# YOTSUBA_GNSS-receiver_Orion_ver_1_6_1.net
KiCad netlist of a schematic drawn in EAGLE
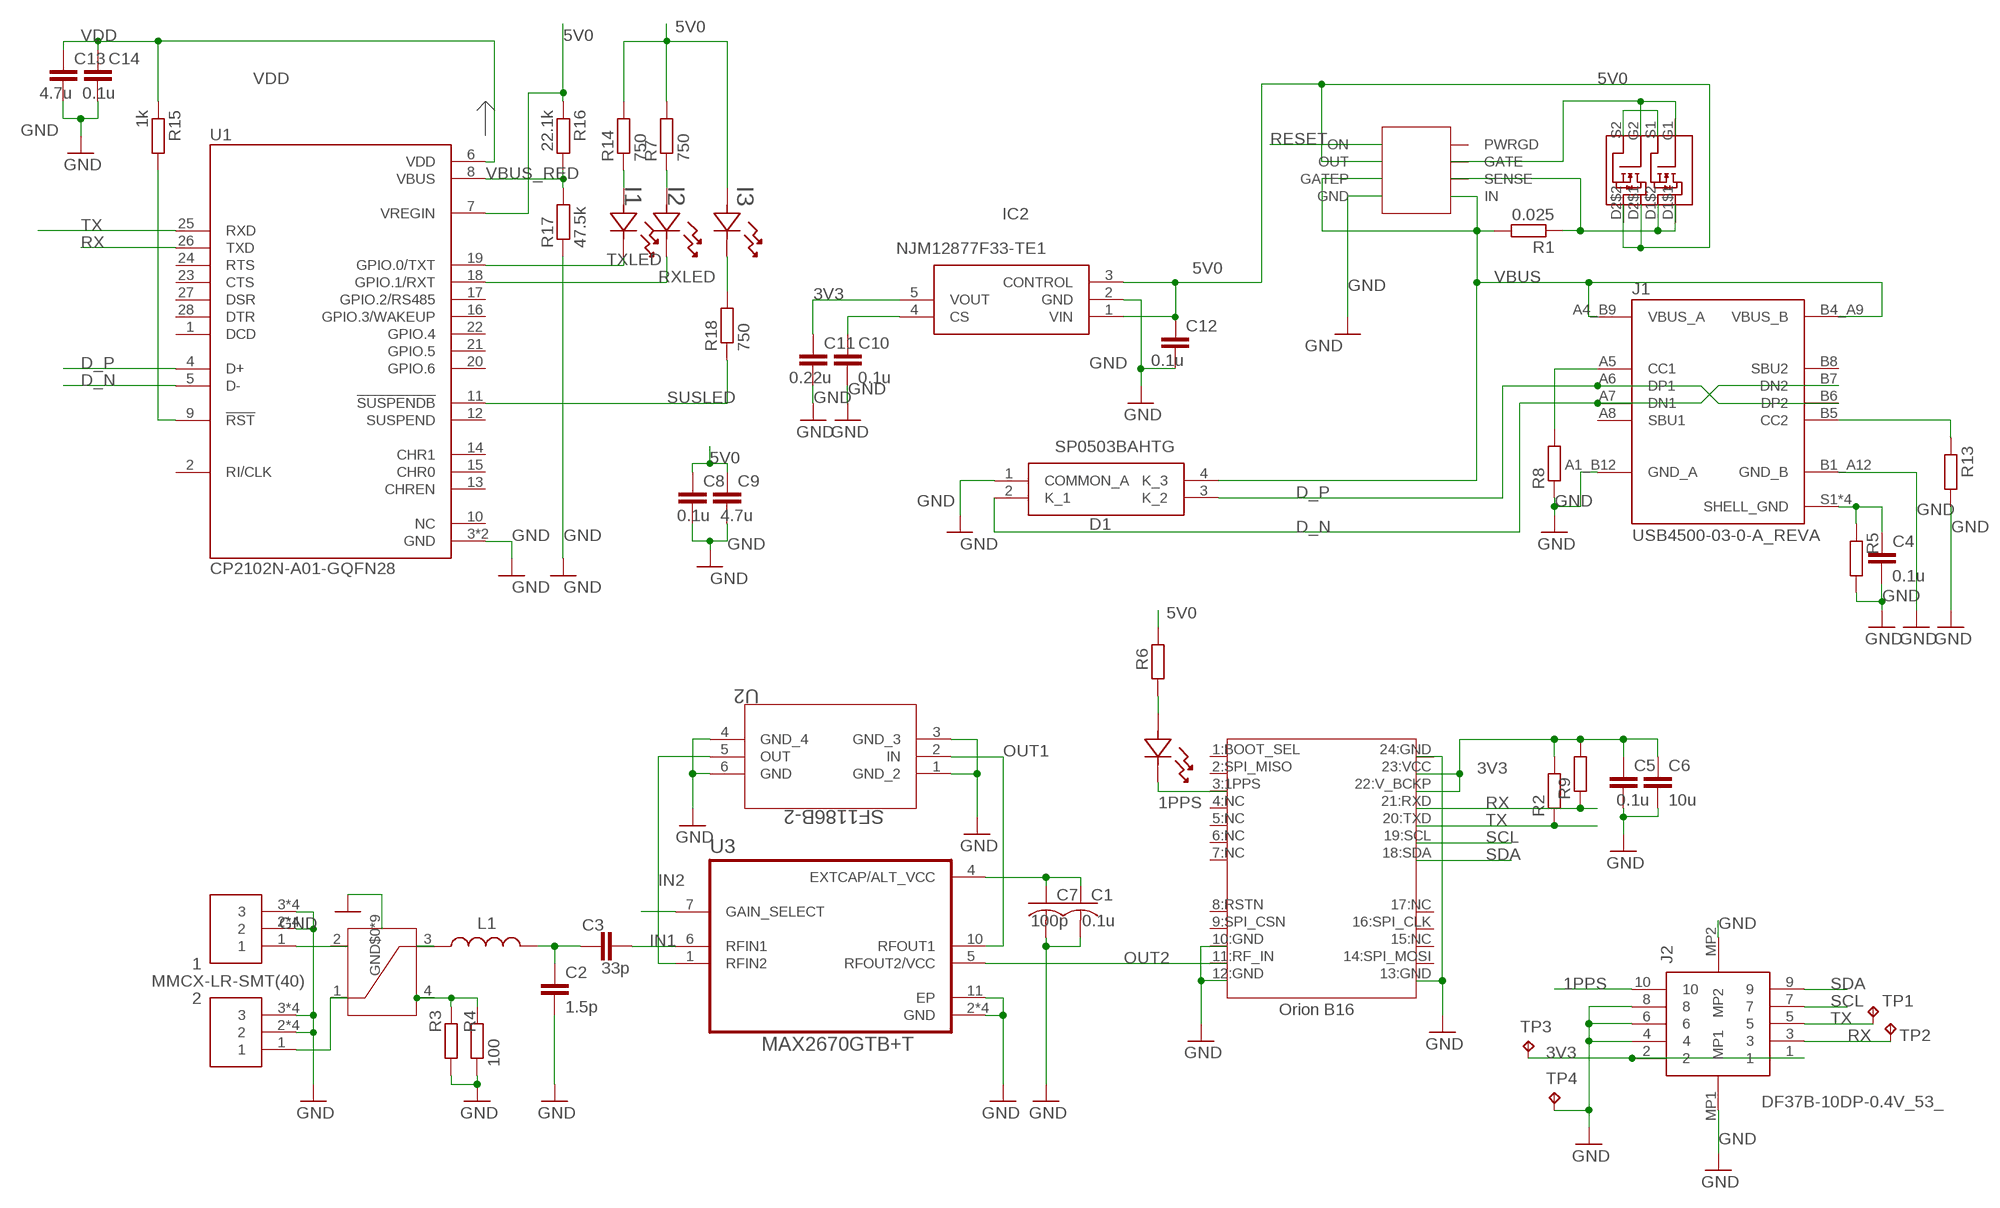
[diagram p0: schematic, sheet 1]

(export (version "E")
  (design (tool "Eeschema 10.0.6"))
  (components
    (comp (ref "1")
      (value "MMCX-LR-SMT(40)")
      (footprint "eagle-import:MMCX-LR-SMT(40)")
      (libsource (lib "eagle-import") (part "MMCX-LR-SMT(40)"))
    )
    (comp (ref "2")
      (value "MMCX-LR-SMT(40)")
      (footprint "eagle-import:MMCX-LR-SMT(40)")
      (libsource (lib "eagle-import") (part "MMCX-LR-SMT(40)"))
    )
    (comp (ref "C1")
      (value "0.1u")
      (footprint "eagle-import:C1608_OS")
      (libsource (lib "eagle-import") (part "C-US"))
    )
    (comp (ref "C2")
      (value "1.5p")
      (footprint "eagle-import:C1608")
      (libsource (lib "eagle-import") (part "C-EUC1608"))
    )
    (comp (ref "C3")
      (value "33p")
      (footprint "eagle-import:C1608")
      (libsource (lib "eagle-import") (part "C-EUC1608"))
    )
    (comp (ref "C4")
      (value "0.1u")
      (footprint "eagle-import:C1608")
      (libsource (lib "eagle-import") (part "C-EUC1608"))
    )
    (comp (ref "C5")
      (value "0.1u")
      (footprint "eagle-import:C1608")
      (libsource (lib "eagle-import") (part "C-EUC1608"))
    )
    (comp (ref "C6")
      (value "10u")
      (footprint "eagle-import:C1608")
      (libsource (lib "eagle-import") (part "C-EUC1608"))
    )
    (comp (ref "C7")
      (value "100p")
      (footprint "eagle-import:C1608_OS")
      (libsource (lib "eagle-import") (part "C-US"))
    )
    (comp (ref "C8")
      (value "0.1u")
      (footprint "eagle-import:C1608")
      (libsource (lib "eagle-import") (part "C-EUC1608"))
    )
    (comp (ref "C9")
      (value "4.7u")
      (footprint "eagle-import:C1608")
      (libsource (lib "eagle-import") (part "C-EUC1608"))
    )
    (comp (ref "C10")
      (value "0.1u")
      (footprint "eagle-import:C1608")
      (libsource (lib "eagle-import") (part "C-EUC1608"))
    )
    (comp (ref "C11")
      (value "0.22u")
      (footprint "eagle-import:C1608")
      (libsource (lib "eagle-import") (part "C-EUC1608"))
    )
    (comp (ref "C12")
      (value "0.1u")
      (footprint "eagle-import:C1608")
      (libsource (lib "eagle-import") (part "C-EUC1608"))
    )
    (comp (ref "C13")
      (value "4.7u")
      (footprint "eagle-import:C1608")
      (libsource (lib "eagle-import") (part "C-EUC1608"))
    )
    (comp (ref "C14")
      (value "0.1u")
      (footprint "eagle-import:C1608")
      (libsource (lib "eagle-import") (part "C-EUC1608"))
    )
    (comp (ref "D1")
      (value "SP0503BAHTG")
      (footprint "eagle-import:SP0503BAHTG")
      (fields (field (name "MOUSER_PART_NUMBER") "576-SP0503BAHTG"))
      (libsource (lib "eagle-import") (part "SP0503BAHTG"))
    )
    (comp (ref "I1")
      (value "SML-E12P8WT86")
      (footprint "eagle-import:LED_SMLD12_ROM")
      (fields (field (name "COPYRIGHT") "Copyright (C) 2023 Ultra Librarian. All rights reserved."))
      (libsource (lib "eagle-import") (part "SML-E12P8WT86"))
    )
    (comp (ref "I2")
      (value "SML-E12P8WT86")
      (footprint "eagle-import:LED_SMLD12_ROM")
      (fields (field (name "COPYRIGHT") "Copyright (C) 2023 Ultra Librarian. All rights reserved."))
      (libsource (lib "eagle-import") (part "SML-E12P8WT86"))
    )
    (comp (ref "I3")
      (value "SML-E12P8WT86")
      (footprint "eagle-import:LED_SMLD12_ROM")
      (fields (field (name "COPYRIGHT") "Copyright (C) 2023 Ultra Librarian. All rights reserved."))
      (libsource (lib "eagle-import") (part "SML-E12P8WT86"))
    )
    (comp (ref "IC2")
      (value "NJM12877F33-TE1")
      (footprint "eagle-import:SOT95P280X120-5N")
      (fields (field (name "MOUSER_PART_NUMBER") "513-NJM12877F33-TE1"))
      (libsource (lib "eagle-import") (part "NJM12877F33-TE1"))
    )
    (comp (ref "J1")
      (value "USB4500-03-0-A_REVA")
      (footprint "eagle-import:GCT_USB4500-03-0-A_REVA")
      (fields
        (field (name "DIGI-KEY_PART_NUMBER") "2073-USB4500-03-0-ATR-ND")
        (field (name "MF") "Global Connector Technology")
        (field (name "MP") "USB4500-03-0-A")
      )
      (libsource (lib "eagle-import") (part "USB4500-03-0-A_REVA"))
    )
    (comp (ref "J2")
      (value "DF37B-10DP-0.4V_53_")
      (footprint "eagle-import:DF37B10DP04V53")
      (fields
        (field (name "MANUFACTURER_PART_NUMBER") "DF37B-10DP-0.4V(53)")
        (field (name "MOUSER_PART_NUMBER") "798-DF37B10DP04V53")
      )
      (libsource (lib "eagle-import") (part "DF37B-10DP-0.4V_53_"))
    )
    (comp (ref "L1")
      (value "4.3n")
      (footprint "eagle-import:INDC1608X100N")
      (fields
        (field (name "DIGIKEY_PART_NUMBER") "490-6896-2-ND")
        (field (name "MF") "Murata")
        (field (name "MP") "LQW18AN4N3C00D")
      )
      (libsource (lib "eagle-import") (part "LQW18AN4N3C00D"))
    )
    (comp (ref "R1")
      (value "0.025")
      (footprint "eagle-import:R0603")
      (libsource (lib "eagle-import") (part "R-EU_R0603"))
    )
    (comp (ref "R2")
      (value "R-EU_R0603")
      (footprint "eagle-import:R0603")
      (libsource (lib "eagle-import") (part "R-EU_R0603"))
    )
    (comp (ref "R3")
      (value "100")
      (footprint "eagle-import:R0603")
      (libsource (lib "eagle-import") (part "R-EU_R0603"))
    )
    (comp (ref "R4")
      (value "100")
      (footprint "eagle-import:R0603")
      (libsource (lib "eagle-import") (part "R-EU_R0603"))
    )
    (comp (ref "R5")
      (value "R-EU_R0603")
      (footprint "eagle-import:R0603")
      (libsource (lib "eagle-import") (part "R-EU_R0603"))
    )
    (comp (ref "R6")
      (value "R-EU_R0603")
      (footprint "eagle-import:R0603")
      (libsource (lib "eagle-import") (part "R-EU_R0603"))
    )
    (comp (ref "R7")
      (value "750")
      (footprint "eagle-import:R0603")
      (libsource (lib "eagle-import") (part "R-EU_R0603"))
    )
    (comp (ref "R8")
      (value "R-EU_R0603")
      (footprint "eagle-import:R0603")
      (libsource (lib "eagle-import") (part "R-EU_R0603"))
    )
    (comp (ref "R9")
      (value "R-EU_R0603")
      (footprint "eagle-import:R0603")
      (libsource (lib "eagle-import") (part "R-EU_R0603"))
    )
    (comp (ref "R10")
      (value "SML-E12P8WT86")
      (footprint "eagle-import:LED_SMLD12_ROM")
      (fields (field (name "COPYRIGHT") "Copyright (C) 2023 Ultra Librarian. All rights reserved."))
      (libsource (lib "eagle-import") (part "SML-E12P8WT86"))
    )
    (comp (ref "R13")
      (value "R-EU_R0603")
      (footprint "eagle-import:R0603")
      (libsource (lib "eagle-import") (part "R-EU_R0603"))
    )
    (comp (ref "R14")
      (value "750")
      (footprint "eagle-import:R0603")
      (libsource (lib "eagle-import") (part "R-EU_R0603"))
    )
    (comp (ref "R15")
      (value "1k")
      (footprint "eagle-import:R0603")
      (libsource (lib "eagle-import") (part "R-EU_R0603"))
    )
    (comp (ref "R16")
      (value "22.1k")
      (footprint "eagle-import:R0603")
      (libsource (lib "eagle-import") (part "R-EU_R0603"))
    )
    (comp (ref "R17")
      (value "47.5k")
      (footprint "eagle-import:R0603")
      (libsource (lib "eagle-import") (part "R-EU_R0603"))
    )
    (comp (ref "R18")
      (value "750")
      (footprint "eagle-import:R0603")
      (libsource (lib "eagle-import") (part "R-EU_R0603"))
    )
    (comp (ref "TP1")
      (value "TPTP13SQ")
      (footprint "eagle-import:TP13SQ")
      (libsource (lib "eagle-import") (part "TPTP13SQ"))
    )
    (comp (ref "TP2")
      (value "TPTP13SQ")
      (footprint "eagle-import:TP13SQ")
      (libsource (lib "eagle-import") (part "TPTP13SQ"))
    )
    (comp (ref "TP3")
      (value "TPTP13SQ")
      (footprint "eagle-import:TP13SQ")
      (libsource (lib "eagle-import") (part "TPTP13SQ"))
    )
    (comp (ref "TP4")
      (value "TPTP13SQ")
      (footprint "eagle-import:TP13SQ")
      (libsource (lib "eagle-import") (part "TPTP13SQ"))
    )
    (comp (ref "U$1")
      (value "ORION_B16")
      (footprint "eagle-import:ORION_B16")
      (libsource (lib "eagle-import") (part "ORION_B16"))
    )
    (comp (ref "U$3")
      (value "HC125.A")
      (footprint "eagle-import:HC125.A")
      (libsource (lib "eagle-import") (part "HC125.A"))
    )
    (comp (ref "U$7")
      (value "DMG6898LSD")
      (footprint "eagle-import:SOIC127P600X150-8N")
      (libsource (lib "eagle-import") (part "DMG6898LSD"))
    )
    (comp (ref "U$8")
      (value "LTC4361")
      (footprint "eagle-import:SOP65P280X100-8N")
      (libsource (lib "eagle-import") (part "LTC4361"))
    )
    (comp (ref "U1")
      (value "CP2102N-A01-GQFN28")
      (footprint "eagle-import:QFN50P500X500X80-29N")
      (fields (field (name "MF") "Silicon Labs"))
      (libsource (lib "eagle-import") (part "CP2102N-A01-GQFN28"))
    )
    (comp (ref "U2")
      (value "SF1186B-2")
      (footprint "eagle-import:SM3030_MUR")
      (fields (field (name "COPYRIGHT") "Copyright (C) 2023 Ultra Librarian. All rights reserved."))
      (libsource (lib "eagle-import") (part "SF1186B-2"))
    )
    (comp (ref "U3")
      (value "MAX2670GTB+T")
      (footprint "eagle-import:DFN300X300X80-11N")
      (fields (field (name "MF") "Analog Devices"))
      (libsource (lib "eagle-import") (part "MAX2670GTB+T"))
    )
  )
  (nets
    (net (code "1") (name "/1PPS") (class "Default")
      (node (ref "J2") (pin "10") (pinfunction "10_10") (pintype "bidirectional"))
      (node (ref "R10") (pin "1") (pinfunction "1_1") (pintype "passive"))
      (node (ref "U$1") (pin "3:1PPS") (pinfunction "3:1PPS_3:1PPS") (pintype "bidirectional"))
    )
    (net (code "2") (name "/3V3") (class "Default")
      (node (ref "C11") (pin "1") (pinfunction "1_1") (pintype "passive"))
      (node (ref "C5") (pin "1") (pinfunction "1_1") (pintype "passive"))
      (node (ref "C6") (pin "1") (pinfunction "1_1") (pintype "passive"))
      (node (ref "IC2") (pin "5") (pinfunction "VOUT_5") (pintype "bidirectional"))
      (node (ref "J2") (pin "1") (pinfunction "1_1") (pintype "bidirectional"))
      (node (ref "J2") (pin "2") (pinfunction "2_2") (pintype "bidirectional"))
      (node (ref "R2") (pin "2") (pinfunction "2_2") (pintype "passive"))
      (node (ref "R9") (pin "2") (pinfunction "2_2") (pintype "passive"))
      (node (ref "TP3") (pin "TP") (pinfunction "TP_TP") (pintype "input"))
      (node (ref "U$1") (pin "22:V_BCKP") (pinfunction "22:V_BCKP_22:V_BCKP") (pintype "bidirectional"))
      (node (ref "U$1") (pin "23:VCC") (pinfunction "23:VCC_23:VCC") (pintype "bidirectional"))
    )
    (net (code "3") (name "/5V0") (class "Default")
      (node (ref "C12") (pin "1") (pinfunction "1_1") (pintype "passive"))
      (node (ref "C8") (pin "1") (pinfunction "1_1") (pintype "passive"))
      (node (ref "C9") (pin "1") (pinfunction "1_1") (pintype "passive"))
      (node (ref "I3") (pin "2") (pinfunction "2_2") (pintype "passive"))
      (node (ref "IC2") (pin "1") (pinfunction "VIN_1") (pintype "bidirectional"))
      (node (ref "IC2") (pin "3") (pinfunction "CONTROL_3") (pintype "bidirectional"))
      (node (ref "R14") (pin "2") (pinfunction "2_2") (pintype "passive"))
      (node (ref "R16") (pin "1") (pinfunction "1_1") (pintype "passive"))
      (node (ref "R6") (pin "2") (pinfunction "2_2") (pintype "passive"))
      (node (ref "R7") (pin "2") (pinfunction "2_2") (pintype "passive"))
      (node (ref "U$7") (pin "D2$1") (pinfunction "D2$1_D2$1") (pintype "bidirectional"))
      (node (ref "U$7") (pin "D2$2") (pinfunction "D2$2_D2$2") (pintype "bidirectional"))
      (node (ref "U$8") (pin "OUT") (pinfunction "OUT_OUT") (pintype "bidirectional"))
      (node (ref "U1") (pin "7") (pinfunction "VREGIN_7") (pintype "power_in"))
    )
    (net (code "4") (name "/D_N") (class "Default")
      (node (ref "D1") (pin "2") (pinfunction "K_1_2") (pintype "bidirectional"))
      (node (ref "J1") (pin "A7") (pinfunction "DN1_A7") (pintype "bidirectional"))
      (node (ref "J1") (pin "B7") (pinfunction "DN2_B7") (pintype "bidirectional"))
      (node (ref "U1") (pin "5") (pinfunction "D-_5") (pintype "bidirectional"))
    )
    (net (code "5") (name "/D_P") (class "Default")
      (node (ref "D1") (pin "3") (pinfunction "K_2_3") (pintype "bidirectional"))
      (node (ref "J1") (pin "A6") (pinfunction "DP1_A6") (pintype "bidirectional"))
      (node (ref "J1") (pin "B6") (pinfunction "DP2_B6") (pintype "bidirectional"))
      (node (ref "U1") (pin "4") (pinfunction "D+_4") (pintype "bidirectional"))
    )
    (net (code "6") (name "/IN1") (class "Default")
      (node (ref "C3") (pin "2") (pinfunction "2_2") (pintype "passive"))
      (node (ref "U3") (pin "6") (pinfunction "RFIN1_6") (pintype "input"))
    )
    (net (code "7") (name "/IN2") (class "Default")
      (node (ref "U2") (pin "5") (pinfunction "OUT_5") (pintype "output"))
      (node (ref "U3") (pin "1") (pinfunction "RFIN2_1") (pintype "input"))
    )
    (net (code "8") (name "/OUT1") (class "Default")
      (node (ref "U2") (pin "2") (pinfunction "IN_2") (pintype "input"))
      (node (ref "U3") (pin "10") (pinfunction "RFOUT1_10") (pintype "output"))
    )
    (net (code "9") (name "/OUT2") (class "Default")
      (node (ref "U$1") (pin "11:RF_IN") (pinfunction "11:RF_IN_11:RF_IN") (pintype "bidirectional"))
      (node (ref "U3") (pin "5") (pinfunction "RFOUT2/VCC_5") (pintype "output"))
    )
    (net (code "10") (name "/RESET") (class "Default")
      (node (ref "U$8") (pin "ON") (pinfunction "ON_ON") (pintype "bidirectional"))
    )
    (net (code "11") (name "/RX") (class "Default")
      (node (ref "J2") (pin "3") (pinfunction "3_3") (pintype "bidirectional"))
      (node (ref "R9") (pin "1") (pinfunction "1_1") (pintype "passive"))
      (node (ref "TP2") (pin "TP") (pinfunction "TP_TP") (pintype "input"))
      (node (ref "U$1") (pin "21:RXD") (pinfunction "21:RXD_21:RXD") (pintype "bidirectional"))
      (node (ref "U1") (pin "26") (pinfunction "TXD_26") (pintype "output"))
    )
    (net (code "12") (name "/RXLED") (class "Default")
      (node (ref "I2") (pin "1") (pinfunction "1_1") (pintype "passive"))
      (node (ref "U1") (pin "18") (pinfunction "GPIO.1/RXT_18") (pintype "bidirectional"))
    )
    (net (code "13") (name "/SCL") (class "Default")
      (node (ref "J2") (pin "7") (pinfunction "7_7") (pintype "bidirectional"))
      (node (ref "U$1") (pin "19:SCL") (pinfunction "19:SCL_19:SCL") (pintype "bidirectional"))
    )
    (net (code "14") (name "/SDA") (class "Default")
      (node (ref "J2") (pin "9") (pinfunction "9_9") (pintype "bidirectional"))
      (node (ref "U$1") (pin "18:SDA") (pinfunction "18:SDA_18:SDA") (pintype "bidirectional"))
    )
    (net (code "15") (name "/SUSLED") (class "Default")
      (node (ref "R18") (pin "1") (pinfunction "1_1") (pintype "passive"))
      (node (ref "U1") (pin "11") (pinfunction "~{SUSPENDB}_11") (pintype "output"))
    )
    (net (code "16") (name "/TX") (class "Default")
      (node (ref "J2") (pin "5") (pinfunction "5_5") (pintype "bidirectional"))
      (node (ref "R2") (pin "1") (pinfunction "1_1") (pintype "passive"))
      (node (ref "TP1") (pin "TP") (pinfunction "TP_TP") (pintype "input"))
      (node (ref "U$1") (pin "20:TXD") (pinfunction "20:TXD_20:TXD") (pintype "bidirectional"))
      (node (ref "U1") (pin "25") (pinfunction "RXD_25") (pintype "input"))
    )
    (net (code "17") (name "/TXLED") (class "Default")
      (node (ref "I1") (pin "1") (pinfunction "1_1") (pintype "passive"))
      (node (ref "U1") (pin "19") (pinfunction "GPIO.0/TXT_19") (pintype "bidirectional"))
    )
    (net (code "18") (name "/VBUS") (class "Default")
      (node (ref "D1") (pin "4") (pinfunction "K_3_4") (pintype "bidirectional"))
      (node (ref "J1") (pin "A4_B9") (pinfunction "VBUS_A_A4_B9") (pintype "power_in"))
      (node (ref "J1") (pin "B4_A9") (pinfunction "VBUS_B_B4_A9") (pintype "power_in"))
      (node (ref "R1") (pin "2") (pinfunction "2_2") (pintype "passive"))
      (node (ref "U$8") (pin "GATEP") (pinfunction "GATEP_GATEP") (pintype "bidirectional"))
      (node (ref "U$8") (pin "IN") (pinfunction "IN_IN") (pintype "bidirectional"))
    )
    (net (code "19") (name "/VBUS_RED") (class "Default")
      (node (ref "R16") (pin "2") (pinfunction "2_2") (pintype "passive"))
      (node (ref "R17") (pin "2") (pinfunction "2_2") (pintype "passive"))
      (node (ref "U1") (pin "8") (pinfunction "VBUS_8") (pintype "power_in"))
    )
    (net (code "20") (name "/VDD") (class "Default")
      (node (ref "C13") (pin "1") (pinfunction "1_1") (pintype "passive"))
      (node (ref "C14") (pin "1") (pinfunction "1_1") (pintype "passive"))
      (node (ref "R15") (pin "1") (pinfunction "1_1") (pintype "passive"))
      (node (ref "U1") (pin "6") (pinfunction "VDD_6") (pintype "power_in"))
    )
    (net (code "21") (name "GND") (class "Default")
      (node (ref "1") (pin "2") (pinfunction "2_2") (pintype "bidirectional"))
      (node (ref "1") (pin "3") (pinfunction "3_3") (pintype "bidirectional"))
      (node (ref "1") (pin "4") (pinfunction "2_4") (pintype "bidirectional"))
      (node (ref "1") (pin "5") (pinfunction "3_5") (pintype "bidirectional"))
      (node (ref "1") (pin "P$1") (pinfunction "2_P$1") (pintype "bidirectional"))
      (node (ref "1") (pin "P$2") (pinfunction "2_P$2") (pintype "bidirectional"))
      (node (ref "1") (pin "P$3") (pinfunction "3_P$3") (pintype "bidirectional"))
      (node (ref "1") (pin "P$4") (pinfunction "3_P$4") (pintype "bidirectional"))
      (node (ref "2") (pin "2") (pinfunction "2_2") (pintype "bidirectional"))
      (node (ref "2") (pin "3") (pinfunction "3_3") (pintype "bidirectional"))
      (node (ref "2") (pin "4") (pinfunction "2_4") (pintype "bidirectional"))
      (node (ref "2") (pin "5") (pinfunction "3_5") (pintype "bidirectional"))
      (node (ref "2") (pin "P$1") (pinfunction "2_P$1") (pintype "bidirectional"))
      (node (ref "2") (pin "P$2") (pinfunction "2_P$2") (pintype "bidirectional"))
      (node (ref "2") (pin "P$3") (pinfunction "3_P$3") (pintype "bidirectional"))
      (node (ref "2") (pin "P$4") (pinfunction "3_P$4") (pintype "bidirectional"))
      (node (ref "C1") (pin "2") (pinfunction "2_2") (pintype "passive"))
      (node (ref "C10") (pin "2") (pinfunction "2_2") (pintype "passive"))
      (node (ref "C11") (pin "2") (pinfunction "2_2") (pintype "passive"))
      (node (ref "C12") (pin "2") (pinfunction "2_2") (pintype "passive"))
      (node (ref "C13") (pin "2") (pinfunction "2_2") (pintype "passive"))
      (node (ref "C14") (pin "2") (pinfunction "2_2") (pintype "passive"))
      (node (ref "C2") (pin "2") (pinfunction "2_2") (pintype "passive"))
      (node (ref "C4") (pin "2") (pinfunction "2_2") (pintype "passive"))
      (node (ref "C5") (pin "2") (pinfunction "2_2") (pintype "passive"))
      (node (ref "C6") (pin "2") (pinfunction "2_2") (pintype "passive"))
      (node (ref "C7") (pin "2") (pinfunction "2_2") (pintype "passive"))
      (node (ref "C8") (pin "2") (pinfunction "2_2") (pintype "passive"))
      (node (ref "C9") (pin "2") (pinfunction "2_2") (pintype "passive"))
      (node (ref "D1") (pin "1") (pinfunction "COMMON_A_1") (pintype "bidirectional"))
      (node (ref "IC2") (pin "2") (pinfunction "GND_2") (pintype "bidirectional"))
      (node (ref "J1") (pin "A1_B12") (pinfunction "GND_A_A1_B12") (pintype "power_in"))
      (node (ref "J1") (pin "B1_A12") (pinfunction "GND_B_B1_A12") (pintype "power_in"))
      (node (ref "J2") (pin "4") (pinfunction "4_4") (pintype "bidirectional"))
      (node (ref "J2") (pin "6") (pinfunction "6_6") (pintype "bidirectional"))
      (node (ref "J2") (pin "8") (pinfunction "8_8") (pintype "bidirectional"))
      (node (ref "J2") (pin "MP1") (pinfunction "MP1_MP1") (pintype "bidirectional"))
      (node (ref "J2") (pin "MP2") (pinfunction "MP2_MP2") (pintype "bidirectional"))
      (node (ref "R13") (pin "2") (pinfunction "2_2") (pintype "passive"))
      (node (ref "R17") (pin "1") (pinfunction "1_1") (pintype "passive"))
      (node (ref "R3") (pin "1") (pinfunction "1_1") (pintype "passive"))
      (node (ref "R4") (pin "1") (pinfunction "1_1") (pintype "passive"))
      (node (ref "R5") (pin "2") (pinfunction "2_2") (pintype "passive"))
      (node (ref "R8") (pin "1") (pinfunction "1_1") (pintype "passive"))
      (node (ref "TP4") (pin "TP") (pinfunction "TP_TP") (pintype "input"))
      (node (ref "U$1") (pin "10:GND") (pinfunction "10:GND_10:GND") (pintype "bidirectional"))
      (node (ref "U$1") (pin "12:GND") (pinfunction "12:GND_12:GND") (pintype "bidirectional"))
      (node (ref "U$1") (pin "13:GND") (pinfunction "13:GND_13:GND") (pintype "bidirectional"))
      (node (ref "U$1") (pin "24:GND") (pinfunction "24:GND_24:GND") (pintype "bidirectional"))
      (node (ref "U$3") (pin "GND$0") (pinfunction "GND_GND$0") (pintype "bidirectional"))
      (node (ref "U$3") (pin "GND$1") (pinfunction "GND_GND$1") (pintype "bidirectional"))
      (node (ref "U$3") (pin "GND$2") (pinfunction "GND_GND$2") (pintype "bidirectional"))
      (node (ref "U$3") (pin "GND$3") (pinfunction "GND_GND$3") (pintype "bidirectional"))
      (node (ref "U$3") (pin "GND$4") (pinfunction "GND_GND$4") (pintype "bidirectional"))
      (node (ref "U$3") (pin "GND$5") (pinfunction "GND_GND$5") (pintype "bidirectional"))
      (node (ref "U$3") (pin "GND$6") (pinfunction "GND_GND$6") (pintype "bidirectional"))
      (node (ref "U$3") (pin "GND$7") (pinfunction "GND_GND$7") (pintype "bidirectional"))
      (node (ref "U$3") (pin "GND$8") (pinfunction "GND_GND$8") (pintype "bidirectional"))
      (node (ref "U$8") (pin "GND") (pinfunction "GND_GND") (pintype "bidirectional"))
      (node (ref "U1") (pin "29") (pinfunction "GND_29") (pintype "power_in"))
      (node (ref "U1") (pin "3") (pinfunction "GND_3") (pintype "power_in"))
      (node (ref "U2") (pin "1") (pinfunction "GND_2_1") (pintype "passive"))
      (node (ref "U2") (pin "3") (pinfunction "GND_3_3") (pintype "passive"))
      (node (ref "U2") (pin "4") (pinfunction "GND_4_4") (pintype "passive"))
      (node (ref "U2") (pin "6") (pinfunction "GND_6") (pintype "passive"))
      (node (ref "U3") (pin "11") (pinfunction "EP_11") (pintype "power_in"))
      (node (ref "U3") (pin "2") (pinfunction "GND_2") (pintype "power_in"))
      (node (ref "U3") (pin "3") (pinfunction "GND_3") (pintype "power_in"))
      (node (ref "U3") (pin "8") (pinfunction "GND_8") (pintype "power_in"))
      (node (ref "U3") (pin "9") (pinfunction "GND_9") (pintype "power_in"))
    )
    (net (code "22") (name "Net-(1-Pad1)") (class "Default")
      (node (ref "1") (pin "1") (pinfunction "1_1") (pintype "bidirectional"))
      (node (ref "U$3") (pin "2") (pinfunction "2_2") (pintype "bidirectional"))
    )
    (net (code "23") (name "Net-(2-Pad1)") (class "Default")
      (node (ref "2") (pin "1") (pinfunction "1_1") (pintype "bidirectional"))
      (node (ref "U$3") (pin "1") (pinfunction "1_1") (pintype "bidirectional"))
    )
    (net (code "24") (name "Net-(C2-Pad1)") (class "Default")
      (node (ref "C2") (pin "1") (pinfunction "1_1") (pintype "passive"))
      (node (ref "C3") (pin "1") (pinfunction "1_1") (pintype "passive"))
      (node (ref "L1") (pin "2") (pinfunction "2_2") (pintype "passive"))
    )
    (net (code "25") (name "Net-(C4-Pad1)") (class "Default")
      (node (ref "C4") (pin "1") (pinfunction "1_1") (pintype "passive"))
      (node (ref "J1") (pin "S1") (pinfunction "SHELL_GND_S1") (pintype "power_in"))
      (node (ref "J1") (pin "S2") (pinfunction "SHELL_GND_S2") (pintype "power_in"))
      (node (ref "J1") (pin "S3") (pinfunction "SHELL_GND_S3") (pintype "power_in"))
      (node (ref "J1") (pin "S4") (pinfunction "SHELL_GND_S4") (pintype "power_in"))
      (node (ref "R5") (pin "1") (pinfunction "1_1") (pintype "passive"))
    )
    (net (code "26") (name "Net-(I1-Pad2)") (class "Default")
      (node (ref "I1") (pin "2") (pinfunction "2_2") (pintype "passive"))
      (node (ref "R14") (pin "1") (pinfunction "1_1") (pintype "passive"))
    )
    (net (code "27") (name "Net-(I2-Pad2)") (class "Default")
      (node (ref "I2") (pin "2") (pinfunction "2_2") (pintype "passive"))
      (node (ref "R7") (pin "1") (pinfunction "1_1") (pintype "passive"))
    )
    (net (code "28") (name "Net-(I3-Pad1)") (class "Default")
      (node (ref "I3") (pin "1") (pinfunction "1_1") (pintype "passive"))
      (node (ref "R18") (pin "2") (pinfunction "2_2") (pintype "passive"))
    )
    (net (code "29") (name "Net-(IC2-CS)") (class "Default")
      (node (ref "C10") (pin "1") (pinfunction "1_1") (pintype "passive"))
      (node (ref "IC2") (pin "4") (pinfunction "CS_4") (pintype "bidirectional"))
    )
    (net (code "30") (name "Net-(J1-CC1)") (class "Default")
      (node (ref "J1") (pin "A5") (pinfunction "CC1_A5") (pintype "bidirectional"))
      (node (ref "R8") (pin "2") (pinfunction "2_2") (pintype "passive"))
    )
    (net (code "31") (name "Net-(J1-CC2)") (class "Default")
      (node (ref "J1") (pin "B5") (pinfunction "CC2_B5") (pintype "bidirectional"))
      (node (ref "R13") (pin "1") (pinfunction "1_1") (pintype "passive"))
    )
    (net (code "32") (name "Net-(L1-Pad1)") (class "Default")
      (node (ref "L1") (pin "1") (pinfunction "1_1") (pintype "passive"))
      (node (ref "U$3") (pin "3") (pinfunction "3_3") (pintype "bidirectional"))
    )
    (net (code "33") (name "Net-(R1-Pad1)") (class "Default")
      (node (ref "R1") (pin "1") (pinfunction "1_1") (pintype "passive"))
      (node (ref "U$7") (pin "D1$1") (pinfunction "D1$1_D1$1") (pintype "bidirectional"))
      (node (ref "U$7") (pin "D1$2") (pinfunction "D1$2_D1$2") (pintype "bidirectional"))
      (node (ref "U$8") (pin "SENSE") (pinfunction "SENSE_SENSE") (pintype "bidirectional"))
    )
    (net (code "34") (name "Net-(R3-Pad2)") (class "Default")
      (node (ref "R3") (pin "2") (pinfunction "2_2") (pintype "passive"))
      (node (ref "R4") (pin "2") (pinfunction "2_2") (pintype "passive"))
      (node (ref "U$3") (pin "4") (pinfunction "4_4") (pintype "bidirectional"))
    )
    (net (code "35") (name "Net-(R10-Pad2)") (class "Default")
      (node (ref "R10") (pin "2") (pinfunction "2_2") (pintype "passive"))
      (node (ref "R6") (pin "1") (pinfunction "1_1") (pintype "passive"))
    )
    (net (code "36") (name "Net-(U$7-PadG1)") (class "Default")
      (node (ref "U$7") (pin "G1") (pinfunction "G1_G1") (pintype "bidirectional"))
      (node (ref "U$7") (pin "G2") (pinfunction "G2_G2") (pintype "bidirectional"))
      (node (ref "U$8") (pin "GATE") (pinfunction "GATE_GATE") (pintype "bidirectional"))
    )
    (net (code "37") (name "Net-(U$7-PadS1)") (class "Default")
      (node (ref "U$7") (pin "S1") (pinfunction "S1_S1") (pintype "bidirectional"))
      (node (ref "U$7") (pin "S2") (pinfunction "S2_S2") (pintype "bidirectional"))
    )
    (net (code "38") (name "Net-(U1-~{RST})") (class "Default")
      (node (ref "R15") (pin "2") (pinfunction "2_2") (pintype "passive"))
      (node (ref "U1") (pin "9") (pinfunction "~{RST}_9") (pintype "input"))
    )
    (net (code "39") (name "Net-(U3-EXTCAP{slash}ALT_VCC)") (class "Default")
      (node (ref "C1") (pin "1") (pinfunction "1_1") (pintype "passive"))
      (node (ref "C7") (pin "1") (pinfunction "1_1") (pintype "passive"))
      (node (ref "U3") (pin "4") (pinfunction "EXTCAP/ALT_VCC_4") (pintype "power_in"))
    )
    (net (code "40") (name "unconnected-(J1-SBU1-PadA8)") (class "Default")
      (node (ref "J1") (pin "A8") (pinfunction "SBU1_A8") (pintype "bidirectional"))
    )
    (net (code "41") (name "unconnected-(J1-SBU2-PadB8)") (class "Default")
      (node (ref "J1") (pin "B8") (pinfunction "SBU2_B8") (pintype "bidirectional"))
    )
    (net (code "42") (name "unconnected-(U$1-Pad1:BOOT_SEL)") (class "Default")
      (node (ref "U$1") (pin "1:BOOT_SEL") (pinfunction "1:BOOT_SEL_1:BOOT_SEL") (pintype "bidirectional"))
    )
    (net (code "43") (name "unconnected-(U$1-Pad2:SPI_MISO)") (class "Default")
      (node (ref "U$1") (pin "2:SPI_MISO") (pinfunction "2:SPI_MISO_2:SPI_MISO") (pintype "bidirectional"))
    )
    (net (code "44") (name "unconnected-(U$1-Pad4:NC)") (class "Default")
      (node (ref "U$1") (pin "4:NC") (pinfunction "4:NC_4:NC") (pintype "bidirectional"))
    )
    (net (code "45") (name "unconnected-(U$1-Pad5:NC)") (class "Default")
      (node (ref "U$1") (pin "5:NC") (pinfunction "5:NC_5:NC") (pintype "bidirectional"))
    )
    (net (code "46") (name "unconnected-(U$1-Pad6:NC)") (class "Default")
      (node (ref "U$1") (pin "6:NC") (pinfunction "6:NC_6:NC") (pintype "bidirectional"))
    )
    (net (code "47") (name "unconnected-(U$1-Pad7:NC)") (class "Default")
      (node (ref "U$1") (pin "7:NC") (pinfunction "7:NC_7:NC") (pintype "bidirectional"))
    )
    (net (code "48") (name "unconnected-(U$1-Pad8:RSTN)") (class "Default")
      (node (ref "U$1") (pin "8:RSTN") (pinfunction "8:RSTN_8:RSTN") (pintype "bidirectional"))
    )
    (net (code "49") (name "unconnected-(U$1-Pad9:SPI_CSN)") (class "Default")
      (node (ref "U$1") (pin "9:SPI_CSN") (pinfunction "9:SPI_CSN_9:SPI_CSN") (pintype "bidirectional"))
    )
    (net (code "50") (name "unconnected-(U$1-Pad14:SPI_MOSI)") (class "Default")
      (node (ref "U$1") (pin "14:SPI_MOSI") (pinfunction "14:SPI_MOSI_14:SPI_MOSI") (pintype "bidirectional"))
    )
    (net (code "51") (name "unconnected-(U$1-Pad15:NC)") (class "Default")
      (node (ref "U$1") (pin "15:NC") (pinfunction "15:NC_15:NC") (pintype "bidirectional"))
    )
    (net (code "52") (name "unconnected-(U$1-Pad16:SPI_CLK)") (class "Default")
      (node (ref "U$1") (pin "16:SPI_CLK") (pinfunction "16:SPI_CLK_16:SPI_CLK") (pintype "bidirectional"))
    )
    (net (code "53") (name "unconnected-(U$1-Pad17:NC)") (class "Default")
      (node (ref "U$1") (pin "17:NC") (pinfunction "17:NC_17:NC") (pintype "bidirectional"))
    )
    (net (code "54") (name "unconnected-(U$8-PadPWRGD)") (class "Default")
      (node (ref "U$8") (pin "PWRGD") (pinfunction "PWRGD_PWRGD") (pintype "bidirectional"))
    )
    (net (code "55") (name "unconnected-(U1-CHR0-Pad15)") (class "Default")
      (node (ref "U1") (pin "15") (pinfunction "CHR0_15") (pintype "output"))
    )
    (net (code "56") (name "unconnected-(U1-CHR1-Pad14)") (class "Default")
      (node (ref "U1") (pin "14") (pinfunction "CHR1_14") (pintype "output"))
    )
    (net (code "57") (name "unconnected-(U1-CHREN-Pad13)") (class "Default")
      (node (ref "U1") (pin "13") (pinfunction "CHREN_13") (pintype "output"))
    )
    (net (code "58") (name "unconnected-(U1-CTS-Pad23)") (class "Default")
      (node (ref "U1") (pin "23") (pinfunction "CTS_23") (pintype "input"))
    )
    (net (code "59") (name "unconnected-(U1-DCD-Pad1)") (class "Default")
      (node (ref "U1") (pin "1") (pinfunction "DCD_1") (pintype "input"))
    )
    (net (code "60") (name "unconnected-(U1-DSR-Pad27)") (class "Default")
      (node (ref "U1") (pin "27") (pinfunction "DSR_27") (pintype "input"))
    )
    (net (code "61") (name "unconnected-(U1-DTR-Pad28)") (class "Default")
      (node (ref "U1") (pin "28") (pinfunction "DTR_28") (pintype "output"))
    )
    (net (code "62") (name "unconnected-(U1-GPIO.2{slash}RS485-Pad17)") (class "Default")
      (node (ref "U1") (pin "17") (pinfunction "GPIO.2/RS485_17") (pintype "bidirectional"))
    )
    (net (code "63") (name "unconnected-(U1-GPIO.3{slash}WAKEUP-Pad16)") (class "Default")
      (node (ref "U1") (pin "16") (pinfunction "GPIO.3/WAKEUP_16") (pintype "bidirectional"))
    )
    (net (code "64") (name "unconnected-(U1-GPIO.4-Pad22)") (class "Default")
      (node (ref "U1") (pin "22") (pinfunction "GPIO.4_22") (pintype "bidirectional"))
    )
    (net (code "65") (name "unconnected-(U1-GPIO.5-Pad21)") (class "Default")
      (node (ref "U1") (pin "21") (pinfunction "GPIO.5_21") (pintype "bidirectional"))
    )
    (net (code "66") (name "unconnected-(U1-GPIO.6-Pad20)") (class "Default")
      (node (ref "U1") (pin "20") (pinfunction "GPIO.6_20") (pintype "bidirectional"))
    )
    (net (code "67") (name "unconnected-(U1-NC-Pad10)") (class "Default")
      (node (ref "U1") (pin "10") (pinfunction "NC_10") (pintype "no_connect"))
    )
    (net (code "68") (name "unconnected-(U1-RI{slash}CLK-Pad2)") (class "Default")
      (node (ref "U1") (pin "2") (pinfunction "RI/CLK_2") (pintype "bidirectional"))
    )
    (net (code "69") (name "unconnected-(U1-RTS-Pad24)") (class "Default")
      (node (ref "U1") (pin "24") (pinfunction "RTS_24") (pintype "output"))
    )
    (net (code "70") (name "unconnected-(U1-SUSPEND-Pad12)") (class "Default")
      (node (ref "U1") (pin "12") (pinfunction "SUSPEND_12") (pintype "output"))
    )
    (net (code "71") (name "unconnected-(U3-GAIN_SELECT-Pad7)") (class "Default")
      (node (ref "U3") (pin "7") (pinfunction "GAIN_SELECT_7") (pintype "input"))
    )
  )
)
